# 10-USB-Prog.net
KiCad netlist of a schematic drawn in Altium Designer
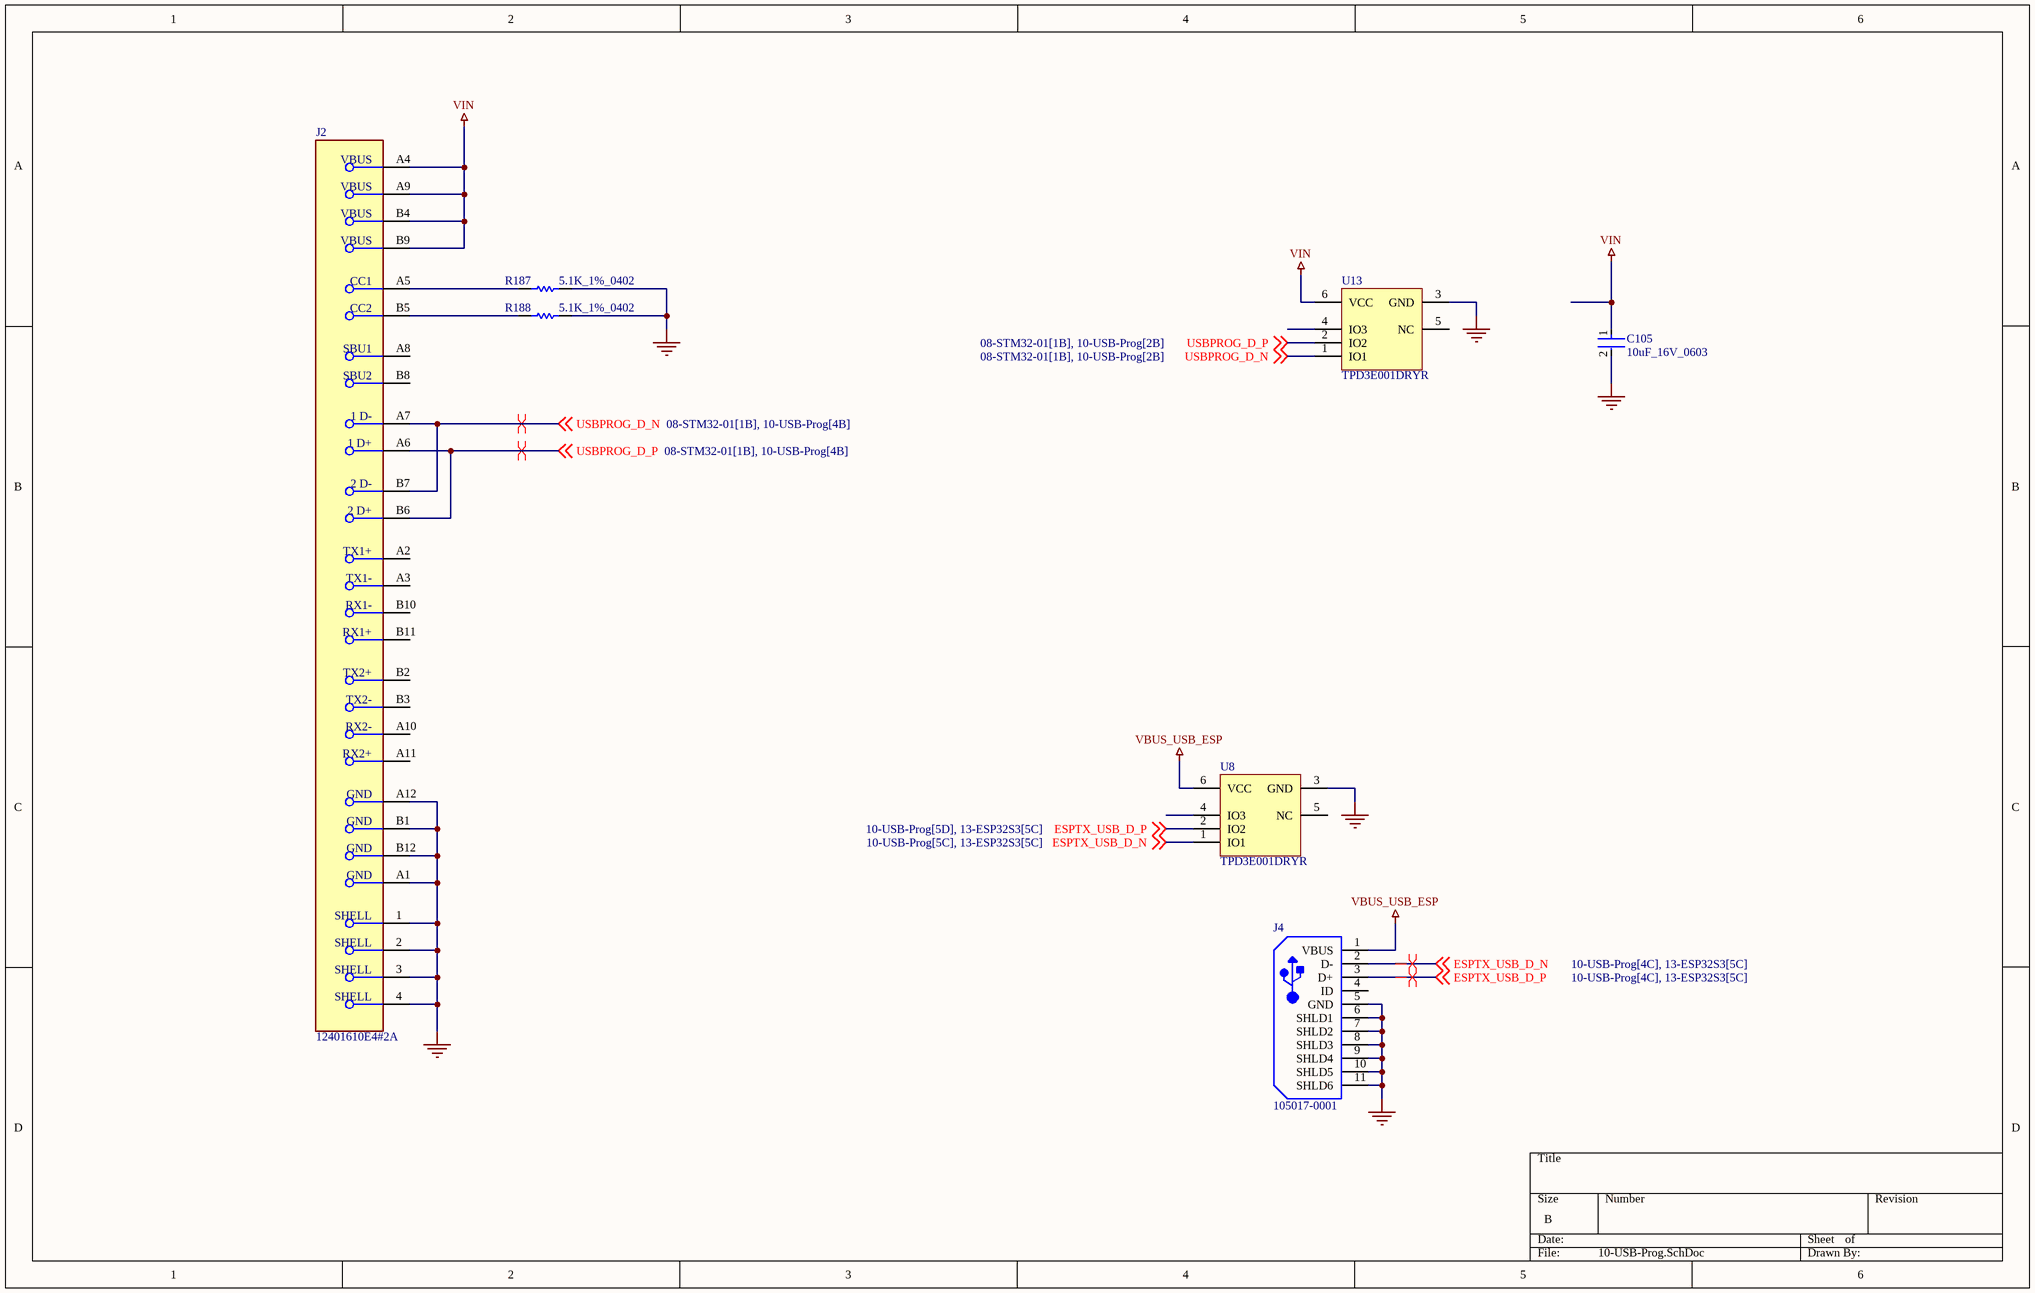
[diagram p0: 10-USB-Prog.SchDoc]

(export (version "E")
  (design (tool "Eeschema 10.0.6"))
  (components
    (comp (ref "C105")
      (value "10uF_16V_0603")
      (footprint "FP-0603-L_1_6_0_2-W_0_8_0-MFG")
      (description "Multilayer Ceramic Capacitor 10uF 16V X5R 20% SMD 0603 T/R")
      (fields (field (name "TOLERANCE") "20%"))
      (libsource (lib "Altium Content Vault") (part "b4654b650e69147ec39a6b967a45e02"))
    )
    (comp (ref "J2")
      (value "12401610E4#2A")
      (footprint "FP-12401610E4#2A-MFG")
      (description "CONN RCP USB3.1 TYPEC 24P SMD RA")
      (libsource (lib "Altium Content Vault") (part "7c76f4c47d7e2af8b8797da79635f2a"))
    )
    (comp (ref "J4")
      (value "105017-0001")
      (footprint "USB-MICRO-B_V")
      (fields (field (name "MANUFACTURER") "Molex"))
      (libsource (lib "Altium Content Vault") (part "USB-5-6SHLD"))
    )
    (comp (ref "R187")
      (value "5.1K_1%_0402")
      (footprint "RESC1005X40X25NL05T10")
      (fields (field (name "PART NUMBER") "RC0402FR-075K1L") (field (name "MANUFACTURER") "Yageo / Phycomp"))
      (libsource (lib "Altium Content Vault") (part "RES"))
    )
    (comp (ref "R188")
      (value "5.1K_1%_0402")
      (footprint "RESC1005X40X25NL05T10")
      (fields (field (name "PART NUMBER") "RC0402FR-075K1L") (field (name "MANUFACTURER") "Yageo / Phycomp"))
      (libsource (lib "Altium Content Vault") (part "RES"))
    )
    (comp (ref "U8")
      (value "TPD3E001DRYR")
      (footprint "DRY0006A")
      (fields (field (name "MANUFACTURER") "Texas Instruments"))
      (libsource (lib "Altium Content Vault") (part "TI-TPD3E001-SON_DRY-6"))
    )
    (comp (ref "U13")
      (value "TPD3E001DRYR")
      (footprint "DRY0006A")
      (fields (field (name "MANUFACTURER") "Texas Instruments"))
      (libsource (lib "Altium Content Vault") (part "TI-TPD3E001-SON_DRY-6"))
    )
  )
  (nets
    (net (code "1") (name "ESPTX_USB_D_N") (class "Default")
      (node (ref "J4") (pin "2") (pinfunction "D-_2") (pintype "passive"))
      (node (ref "U8") (pin "1") (pinfunction "IO1_1") (pintype "passive"))
    )
    (net (code "2") (name "ESPTX_USB_D_P") (class "Default")
      (node (ref "J4") (pin "3") (pinfunction "D+_3") (pintype "passive"))
      (node (ref "U8") (pin "2") (pinfunction "IO2_2") (pintype "passive"))
    )
    (net (code "3") (name "GND") (class "Default")
      (node (ref "C105") (pin "2") (pinfunction "2_2") (pintype "passive"))
      (node (ref "J2") (pin "1") (pinfunction "SHELL_1") (pintype "power_in"))
      (node (ref "J2") (pin "2") (pinfunction "SHELL_2") (pintype "power_in"))
      (node (ref "J2") (pin "3") (pinfunction "SHELL_3") (pintype "power_in"))
      (node (ref "J2") (pin "4") (pinfunction "SHELL_4") (pintype "power_in"))
      (node (ref "J2") (pin "A1") (pinfunction "GND_A1") (pintype "power_in"))
      (node (ref "J2") (pin "A12") (pinfunction "GND_A12") (pintype "power_in"))
      (node (ref "J2") (pin "B1") (pinfunction "GND_B1") (pintype "power_in"))
      (node (ref "J2") (pin "B12") (pinfunction "GND_B12") (pintype "power_in"))
      (node (ref "J4") (pin "10") (pinfunction "SHLD5_10") (pintype "passive"))
      (node (ref "J4") (pin "11") (pinfunction "SHLD6_11") (pintype "passive"))
      (node (ref "J4") (pin "5") (pinfunction "GND_5") (pintype "passive"))
      (node (ref "J4") (pin "6") (pinfunction "SHLD1_6") (pintype "passive"))
      (node (ref "J4") (pin "7") (pinfunction "SHLD2_7") (pintype "passive"))
      (node (ref "J4") (pin "8") (pinfunction "SHLD3_8") (pintype "passive"))
      (node (ref "J4") (pin "9") (pinfunction "SHLD4_9") (pintype "passive"))
      (node (ref "R187") (pin "2") (pinfunction "2_2") (pintype "passive"))
      (node (ref "R188") (pin "2") (pinfunction "2_2") (pintype "passive"))
      (node (ref "U13") (pin "3") (pinfunction "GND_3") (pintype "power_in"))
      (node (ref "U8") (pin "3") (pinfunction "GND_3") (pintype "power_in"))
    )
    (net (code "4") (name "Net-(J2-CC1)") (class "Default")
      (node (ref "J2") (pin "A5") (pinfunction "CC1_A5") (pintype "passive"))
      (node (ref "R187") (pin "1") (pinfunction "1_1") (pintype "passive"))
    )
    (net (code "5") (name "Net-(J2-CC2)") (class "Default")
      (node (ref "J2") (pin "B5") (pinfunction "CC2_B5") (pintype "passive"))
      (node (ref "R188") (pin "1") (pinfunction "1_1") (pintype "passive"))
    )
    (net (code "6") (name "USBPROG_D_N") (class "Default")
      (node (ref "J2") (pin "A7") (pinfunction "1_D-_A7") (pintype "passive"))
      (node (ref "J2") (pin "B7") (pinfunction "2_D-_B7") (pintype "passive"))
      (node (ref "U13") (pin "1") (pinfunction "IO1_1") (pintype "passive"))
    )
    (net (code "7") (name "USBPROG_D_P") (class "Default")
      (node (ref "J2") (pin "A6") (pinfunction "1_D+_A6") (pintype "passive"))
      (node (ref "J2") (pin "B6") (pinfunction "2_D+_B6") (pintype "passive"))
      (node (ref "U13") (pin "2") (pinfunction "IO2_2") (pintype "passive"))
    )
    (net (code "8") (name "VBUS_USB_ESP") (class "Default")
      (node (ref "J4") (pin "1") (pinfunction "VBUS_1") (pintype "passive"))
      (node (ref "U8") (pin "6") (pinfunction "VCC_6") (pintype "power_in"))
    )
    (net (code "9") (name "VIN") (class "Default")
      (node (ref "C105") (pin "1") (pinfunction "1_1") (pintype "passive"))
      (node (ref "J2") (pin "A4") (pinfunction "VBUS_A4") (pintype "power_in"))
      (node (ref "J2") (pin "A9") (pinfunction "VBUS_A9") (pintype "power_in"))
      (node (ref "J2") (pin "B4") (pinfunction "VBUS_B4") (pintype "power_in"))
      (node (ref "J2") (pin "B9") (pinfunction "VBUS_B9") (pintype "power_in"))
      (node (ref "U13") (pin "6") (pinfunction "VCC_6") (pintype "power_in"))
    )
    (net (code "10") (name "unconnected-(J2-RX1+-PadB11)") (class "Default")
      (node (ref "J2") (pin "B11") (pinfunction "RX1+_B11") (pintype "passive"))
    )
    (net (code "11") (name "unconnected-(J2-RX1--PadB10)") (class "Default")
      (node (ref "J2") (pin "B10") (pinfunction "RX1-_B10") (pintype "passive"))
    )
    (net (code "12") (name "unconnected-(J2-RX2+-PadA11)") (class "Default")
      (node (ref "J2") (pin "A11") (pinfunction "RX2+_A11") (pintype "passive"))
    )
    (net (code "13") (name "unconnected-(J2-RX2--PadA10)") (class "Default")
      (node (ref "J2") (pin "A10") (pinfunction "RX2-_A10") (pintype "passive"))
    )
    (net (code "14") (name "unconnected-(J2-SBU1-PadA8)") (class "Default")
      (node (ref "J2") (pin "A8") (pinfunction "SBU1_A8") (pintype "passive"))
    )
    (net (code "15") (name "unconnected-(J2-SBU2-PadB8)") (class "Default")
      (node (ref "J2") (pin "B8") (pinfunction "SBU2_B8") (pintype "passive"))
    )
    (net (code "16") (name "unconnected-(J2-TX1+-PadA2)") (class "Default")
      (node (ref "J2") (pin "A2") (pinfunction "TX1+_A2") (pintype "passive"))
    )
    (net (code "17") (name "unconnected-(J2-TX1--PadA3)") (class "Default")
      (node (ref "J2") (pin "A3") (pinfunction "TX1-_A3") (pintype "passive"))
    )
    (net (code "18") (name "unconnected-(J2-TX2+-PadB2)") (class "Default")
      (node (ref "J2") (pin "B2") (pinfunction "TX2+_B2") (pintype "passive"))
    )
    (net (code "19") (name "unconnected-(J2-TX2--PadB3)") (class "Default")
      (node (ref "J2") (pin "B3") (pinfunction "TX2-_B3") (pintype "passive"))
    )
    (net (code "20") (name "unconnected-(J4-ID-Pad4)") (class "Default")
      (node (ref "J4") (pin "4") (pinfunction "ID_4") (pintype "passive"))
    )
    (net (code "21") (name "unconnected-(U8-IO3-Pad4)") (class "Default")
      (node (ref "U8") (pin "4") (pinfunction "IO3_4") (pintype "passive"))
    )
    (net (code "22") (name "unconnected-(U8-NC-Pad5)") (class "Default")
      (node (ref "U8") (pin "5") (pinfunction "NC_5") (pintype "passive"))
    )
    (net (code "23") (name "unconnected-(U13-IO3-Pad4)") (class "Default")
      (node (ref "U13") (pin "4") (pinfunction "IO3_4") (pintype "passive"))
    )
    (net (code "24") (name "unconnected-(U13-NC-Pad5)") (class "Default")
      (node (ref "U13") (pin "5") (pinfunction "NC_5") (pintype "passive"))
    )
  )
)
